# FXIMU.net
KiCad netlist of a schematic drawn in EAGLE
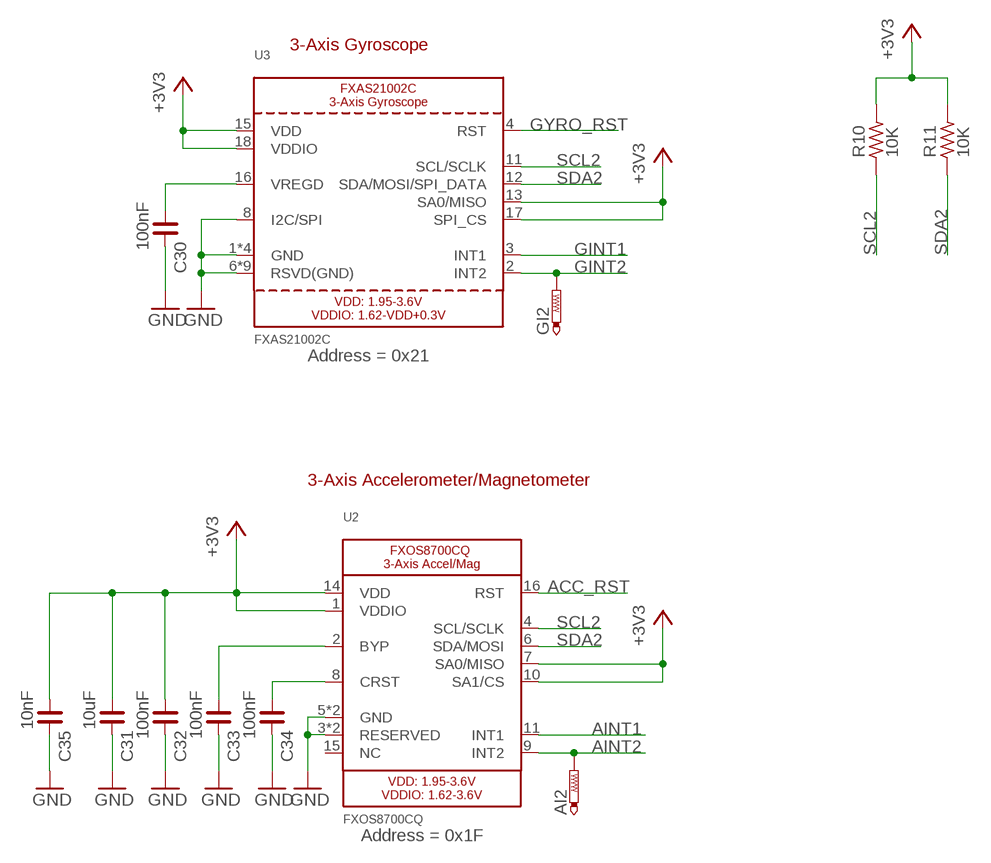
[diagram p0: schematic, sheet 1]
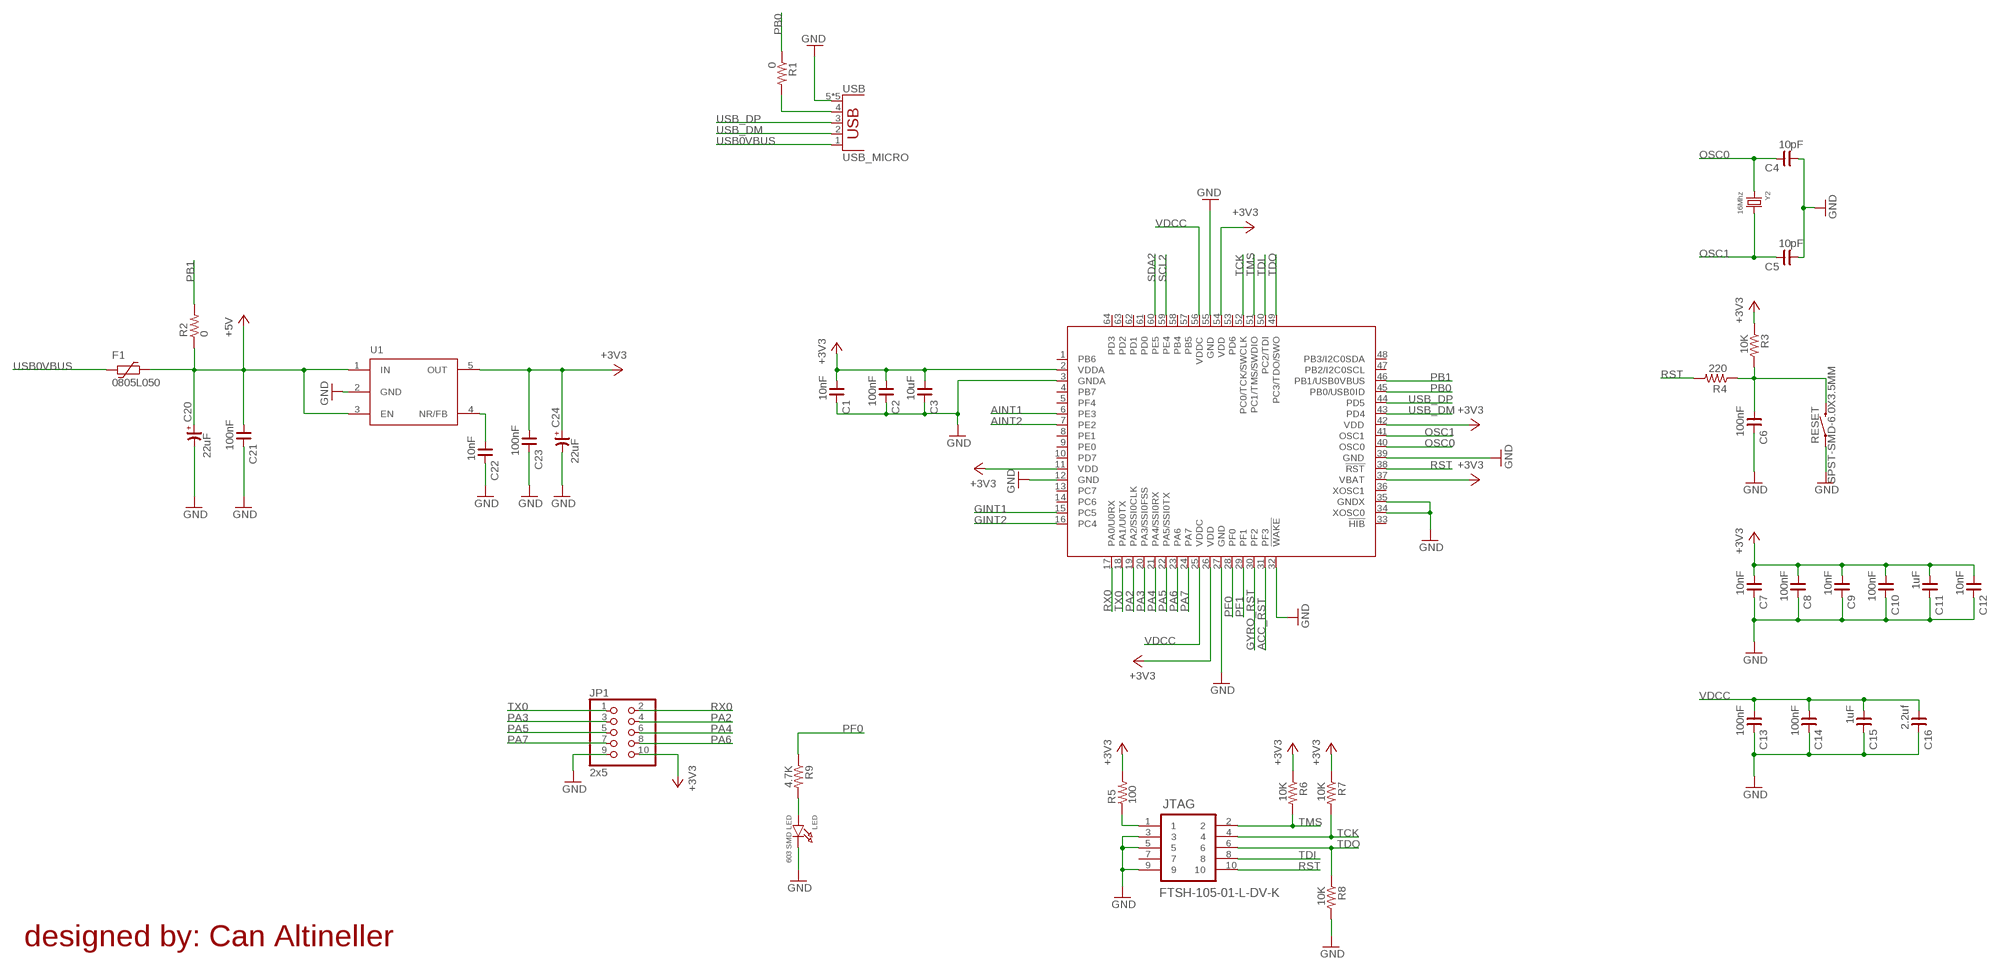
[diagram p1: schematic, sheet 2]

(export (version "E")
  (design (tool "Eeschema 10.0.6"))
  (components
    (comp (ref "AI2")
      (value "PTR1TP06R")
      (footprint "eagle-import:TP06R")
      (libsource (lib "eagle-import") (part "PTR1TP06R"))
    )
    (comp (ref "C30")
      (value "100nF")
      (footprint "eagle-import:C0402")
      (libsource (lib "eagle-import") (part "C_0402"))
    )
    (comp (ref "C31")
      (value "10uF")
      (footprint "eagle-import:C0603")
      (libsource (lib "eagle-import") (part "C_0603"))
    )
    (comp (ref "C32")
      (value "100nF")
      (footprint "eagle-import:C0402")
      (libsource (lib "eagle-import") (part "C_0402"))
    )
    (comp (ref "C33")
      (value "100nF")
      (footprint "eagle-import:C0402")
      (libsource (lib "eagle-import") (part "C_0402"))
    )
    (comp (ref "C34")
      (value "100nF")
      (footprint "eagle-import:C0402")
      (libsource (lib "eagle-import") (part "C_0402"))
    )
    (comp (ref "C35")
      (value "10nF")
      (footprint "eagle-import:C0402")
      (libsource (lib "eagle-import") (part "C_0402"))
    )
    (comp (ref "GI2")
      (value "PTR1TP06R")
      (footprint "eagle-import:TP06R")
      (libsource (lib "eagle-import") (part "PTR1TP06R"))
    )
    (comp (ref "R10")
      (value "10K")
      (footprint "eagle-import:R0402")
      (libsource (lib "eagle-import") (part "R_0402"))
    )
    (comp (ref "R11")
      (value "10K")
      (footprint "eagle-import:R0402")
      (libsource (lib "eagle-import") (part "R_0402"))
    )
    (comp (ref "U2")
      (value "FXOS8700CQ")
      (footprint "eagle-import:QFN16_3MM_FREESCALE_5X3")
      (libsource (lib "eagle-import") (part "ACCEL_MAG_FXOS8700CQ"))
    )
    (comp (ref "U3")
      (value "FXAS21002C")
      (footprint "eagle-import:QFN24_4MM_FREESCALE_7X5")
      (libsource (lib "eagle-import") (part "GYRO_FXAS21002C"))
    )
    (comp (ref "C1")
      (value "10nF")
      (footprint "eagle-import:C0402")
      (libsource (lib "eagle-import") (part "C_0402"))
    )
    (comp (ref "C2")
      (value "100nF")
      (footprint "eagle-import:C0402")
      (libsource (lib "eagle-import") (part "C_0402"))
    )
    (comp (ref "C3")
      (value "10uF")
      (footprint "eagle-import:C0603")
      (libsource (lib "eagle-import") (part "C_0603"))
    )
    (comp (ref "C4")
      (value "10pF")
      (footprint "eagle-import:C0402")
      (libsource (lib "eagle-import") (part "C_0402"))
    )
    (comp (ref "C5")
      (value "10pF")
      (footprint "eagle-import:C0402")
      (libsource (lib "eagle-import") (part "C_0402"))
    )
    (comp (ref "C6")
      (value "100nF")
      (footprint "eagle-import:C0402")
      (libsource (lib "eagle-import") (part "C_0402"))
    )
    (comp (ref "C7")
      (value "10nF")
      (footprint "eagle-import:C0402")
      (libsource (lib "eagle-import") (part "C_0402"))
    )
    (comp (ref "C8")
      (value "100nF")
      (footprint "eagle-import:C0402")
      (libsource (lib "eagle-import") (part "C_0402"))
    )
    (comp (ref "C9")
      (value "10nF")
      (footprint "eagle-import:C0402")
      (libsource (lib "eagle-import") (part "C_0402"))
    )
    (comp (ref "C10")
      (value "100nF")
      (footprint "eagle-import:C0402")
      (libsource (lib "eagle-import") (part "C_0402"))
    )
    (comp (ref "C11")
      (value "1uF")
      (footprint "eagle-import:C0402")
      (libsource (lib "eagle-import") (part "C_0402"))
    )
    (comp (ref "C12")
      (value "10nF")
      (footprint "eagle-import:C0402")
      (libsource (lib "eagle-import") (part "C_0402"))
    )
    (comp (ref "C13")
      (value "100nF")
      (footprint "eagle-import:C0402")
      (libsource (lib "eagle-import") (part "C_0402"))
    )
    (comp (ref "C14")
      (value "100nF")
      (footprint "eagle-import:C0402")
      (libsource (lib "eagle-import") (part "C_0402"))
    )
    (comp (ref "C15")
      (value "1uF")
      (footprint "eagle-import:C0402")
      (libsource (lib "eagle-import") (part "C_0402"))
    )
    (comp (ref "C16")
      (value "2.2uf")
      (footprint "eagle-import:C0603")
      (libsource (lib "eagle-import") (part "C_0603"))
    )
    (comp (ref "C20")
      (value "22uF")
      (footprint "eagle-import:C3528-21_T")
      (libsource (lib "eagle-import") (part "CP_3528-21"))
    )
    (comp (ref "C21")
      (value "100nF")
      (footprint "eagle-import:C0402")
      (libsource (lib "eagle-import") (part "C_0402"))
    )
    (comp (ref "C22")
      (value "10nF")
      (footprint "eagle-import:C0402")
      (libsource (lib "eagle-import") (part "C_0402"))
    )
    (comp (ref "C23")
      (value "100nF")
      (footprint "eagle-import:C0402")
      (libsource (lib "eagle-import") (part "C_0402"))
    )
    (comp (ref "C24")
      (value "22uF")
      (footprint "eagle-import:C3528-21_T")
      (libsource (lib "eagle-import") (part "CP_3528-21"))
    )
    (comp (ref "F1")
      (value "0805L050")
      (footprint "eagle-import:0805L")
      (fields (field (name "MF") "Littelfuse"))
      (libsource (lib "eagle-import") (part "?0805L050"))
    )
    (comp (ref "IC1")
      (value "TM4C123[7,G]XXPM")
      (footprint "eagle-import:PM_S-PQFP-G64")
      (libsource (lib "eagle-import") (part "TM4C123[7,G]XXPM"))
    )
    (comp (ref "JP1")
      (value "2x5")
      (footprint "eagle-import:2X05")
      (libsource (lib "eagle-import") (part "PINHD-2X5"))
    )
    (comp (ref "JTAG")
      (value "FTSH-105-01-L-DV-K")
      (footprint "eagle-import:SAMTEC_FTSH-105-01-L-DV-K")
      (fields (field (name "MF") "Samtec"))
      (libsource (lib "eagle-import") (part "FTSH-105-01-L-DV-K"))
    )
    (comp (ref "LED")
      (value "603 SMD LED")
      (footprint "eagle-import:CHIPLED_0603")
      (libsource (lib "eagle-import") (part "LED0603"))
    )
    (comp (ref "R1")
      (value "0")
      (footprint "eagle-import:R0402")
      (libsource (lib "eagle-import") (part "R_0402"))
    )
    (comp (ref "R2")
      (value "0")
      (footprint "eagle-import:R0402")
      (libsource (lib "eagle-import") (part "R_0402"))
    )
    (comp (ref "R3")
      (value "10K")
      (footprint "eagle-import:R0402")
      (libsource (lib "eagle-import") (part "R_0402"))
    )
    (comp (ref "R4")
      (value "220")
      (footprint "eagle-import:R0402")
      (libsource (lib "eagle-import") (part "R_0402"))
    )
    (comp (ref "R5")
      (value "100")
      (footprint "eagle-import:R0402")
      (libsource (lib "eagle-import") (part "R_0402"))
    )
    (comp (ref "R6")
      (value "10K")
      (footprint "eagle-import:R0402")
      (libsource (lib "eagle-import") (part "R_0402"))
    )
    (comp (ref "R7")
      (value "10K")
      (footprint "eagle-import:R0402")
      (libsource (lib "eagle-import") (part "R_0402"))
    )
    (comp (ref "R8")
      (value "10K")
      (footprint "eagle-import:R0402")
      (libsource (lib "eagle-import") (part "R_0402"))
    )
    (comp (ref "R9")
      (value "4.7K")
      (footprint "eagle-import:R0402")
      (libsource (lib "eagle-import") (part "R_0402"))
    )
    (comp (ref "RESET")
      (value "SPST-SMD-6.0X3.5MM")
      (footprint "eagle-import:TACTILE_SWITCH_SMD_6.0X3.5MM")
      (libsource (lib "eagle-import") (part "MOMENTARY-SWITCH-SPST-SMD-6.0X3.5MM"))
    )
    (comp (ref "U1")
      (value "TPS73633")
      (footprint "eagle-import:SOT23-5L")
      (libsource (lib "eagle-import") (part "TPS73633"))
    )
    (comp (ref "USB")
      (value "USB_MICRO")
      (footprint "eagle-import:USB_MICRO_MOLEX_FULL")
      (libsource (lib "eagle-import") (part "USB_MICRO"))
    )
    (comp (ref "Y2")
      (value "16Mhz")
      (footprint "eagle-import:6X3.3MM")
      (libsource (lib "eagle-import") (part "CRYSTAL.6X3.3MM"))
    )
  )
  (nets
    (net (code "1") (name "+3V3") (class "Default")
      (node (ref "C1") (pin "1") (pinfunction "1_1") (pintype "passive"))
      (node (ref "C10") (pin "1") (pinfunction "1_1") (pintype "passive"))
      (node (ref "C11") (pin "1") (pinfunction "1_1") (pintype "passive"))
      (node (ref "C12") (pin "1") (pinfunction "1_1") (pintype "passive"))
      (node (ref "C2") (pin "1") (pinfunction "1_1") (pintype "passive"))
      (node (ref "C23") (pin "1") (pinfunction "1_1") (pintype "passive"))
      (node (ref "C24") (pin "+") (pinfunction "+_+") (pintype "passive"))
      (node (ref "C3") (pin "1") (pinfunction "1_1") (pintype "passive"))
      (node (ref "C31") (pin "1") (pinfunction "1_1") (pintype "passive"))
      (node (ref "C32") (pin "1") (pinfunction "1_1") (pintype "passive"))
      (node (ref "C35") (pin "1") (pinfunction "1_1") (pintype "passive"))
      (node (ref "C7") (pin "1") (pinfunction "1_1") (pintype "passive"))
      (node (ref "C8") (pin "1") (pinfunction "1_1") (pintype "passive"))
      (node (ref "C9") (pin "1") (pinfunction "1_1") (pintype "passive"))
      (node (ref "IC1") (pin "11") (pinfunction "VDD_11") (pintype "bidirectional"))
      (node (ref "IC1") (pin "2") (pinfunction "VDDA_2") (pintype "bidirectional"))
      (node (ref "IC1") (pin "26") (pinfunction "VDD_26") (pintype "bidirectional"))
      (node (ref "IC1") (pin "37") (pinfunction "VBAT_37") (pintype "bidirectional"))
      (node (ref "IC1") (pin "42") (pinfunction "VDD_42") (pintype "bidirectional"))
      (node (ref "IC1") (pin "54") (pinfunction "VDD_54") (pintype "bidirectional"))
      (node (ref "JP1") (pin "10") (pinfunction "10_10") (pintype "passive"))
      (node (ref "R10") (pin "2") (pinfunction "2_2") (pintype "passive"))
      (node (ref "R11") (pin "2") (pinfunction "2_2") (pintype "passive"))
      (node (ref "R3") (pin "1") (pinfunction "1_1") (pintype "passive"))
      (node (ref "R5") (pin "2") (pinfunction "2_2") (pintype "passive"))
      (node (ref "R6") (pin "1") (pinfunction "1_1") (pintype "passive"))
      (node (ref "R7") (pin "1") (pinfunction "1_1") (pintype "passive"))
      (node (ref "U1") (pin "5") (pinfunction "OUT_5") (pintype "bidirectional"))
      (node (ref "U2") (pin "1") (pinfunction "VDDIO_1") (pintype "bidirectional"))
      (node (ref "U2") (pin "10") (pinfunction "SA1/CS_10") (pintype "bidirectional"))
      (node (ref "U2") (pin "14") (pinfunction "VDD_14") (pintype "bidirectional"))
      (node (ref "U2") (pin "7") (pinfunction "SA0/MISO_7") (pintype "bidirectional"))
      (node (ref "U3") (pin "13") (pinfunction "SA0/MISO_13") (pintype "bidirectional"))
      (node (ref "U3") (pin "15") (pinfunction "VDD_15") (pintype "bidirectional"))
      (node (ref "U3") (pin "17") (pinfunction "SPI_CS_17") (pintype "bidirectional"))
      (node (ref "U3") (pin "18") (pinfunction "VDDIO_18") (pintype "bidirectional"))
    )
    (net (code "2") (name "+5V") (class "Default")
      (node (ref "C20") (pin "+") (pinfunction "+_+") (pintype "passive"))
      (node (ref "C21") (pin "1") (pinfunction "1_1") (pintype "passive"))
      (node (ref "F1") (pin "1") (pinfunction "1_1") (pintype "passive"))
      (node (ref "R2") (pin "1") (pinfunction "1_1") (pintype "passive"))
      (node (ref "U1") (pin "1") (pinfunction "IN_1") (pintype "bidirectional"))
      (node (ref "U1") (pin "3") (pinfunction "EN_3") (pintype "bidirectional"))
    )
    (net (code "3") (name "ACC_RST") (class "Default")
      (node (ref "IC1") (pin "31") (pinfunction "PF3_31") (pintype "bidirectional"))
      (node (ref "U2") (pin "16") (pinfunction "RST_16") (pintype "bidirectional"))
    )
    (net (code "4") (name "AINT1") (class "Default")
      (node (ref "IC1") (pin "6") (pinfunction "PE3_6") (pintype "bidirectional"))
      (node (ref "U2") (pin "11") (pinfunction "INT1_11") (pintype "bidirectional"))
    )
    (net (code "5") (name "AINT2") (class "Default")
      (node (ref "AI2") (pin "TP") (pinfunction "TP_TP") (pintype "input"))
      (node (ref "IC1") (pin "7") (pinfunction "PE2_7") (pintype "bidirectional"))
      (node (ref "U2") (pin "9") (pinfunction "INT2_9") (pintype "bidirectional"))
    )
    (net (code "6") (name "GINT1") (class "Default")
      (node (ref "IC1") (pin "15") (pinfunction "PC5_15") (pintype "bidirectional"))
      (node (ref "U3") (pin "3") (pinfunction "INT1_3") (pintype "bidirectional"))
    )
    (net (code "7") (name "GINT2") (class "Default")
      (node (ref "GI2") (pin "TP") (pinfunction "TP_TP") (pintype "input"))
      (node (ref "IC1") (pin "16") (pinfunction "PC4_16") (pintype "bidirectional"))
      (node (ref "U3") (pin "2") (pinfunction "INT2_2") (pintype "bidirectional"))
    )
    (net (code "8") (name "GND") (class "Default")
      (node (ref "C1") (pin "2") (pinfunction "2_2") (pintype "passive"))
      (node (ref "C10") (pin "2") (pinfunction "2_2") (pintype "passive"))
      (node (ref "C11") (pin "2") (pinfunction "2_2") (pintype "passive"))
      (node (ref "C12") (pin "2") (pinfunction "2_2") (pintype "passive"))
      (node (ref "C13") (pin "2") (pinfunction "2_2") (pintype "passive"))
      (node (ref "C14") (pin "2") (pinfunction "2_2") (pintype "passive"))
      (node (ref "C15") (pin "2") (pinfunction "2_2") (pintype "passive"))
      (node (ref "C16") (pin "2") (pinfunction "2_2") (pintype "passive"))
      (node (ref "C2") (pin "2") (pinfunction "2_2") (pintype "passive"))
      (node (ref "C20") (pin "-") (pinfunction "-_-") (pintype "passive"))
      (node (ref "C21") (pin "2") (pinfunction "2_2") (pintype "passive"))
      (node (ref "C22") (pin "2") (pinfunction "2_2") (pintype "passive"))
      (node (ref "C23") (pin "2") (pinfunction "2_2") (pintype "passive"))
      (node (ref "C24") (pin "-") (pinfunction "-_-") (pintype "passive"))
      (node (ref "C3") (pin "2") (pinfunction "2_2") (pintype "passive"))
      (node (ref "C30") (pin "2") (pinfunction "2_2") (pintype "passive"))
      (node (ref "C31") (pin "2") (pinfunction "2_2") (pintype "passive"))
      (node (ref "C32") (pin "2") (pinfunction "2_2") (pintype "passive"))
      (node (ref "C33") (pin "2") (pinfunction "2_2") (pintype "passive"))
      (node (ref "C34") (pin "2") (pinfunction "2_2") (pintype "passive"))
      (node (ref "C35") (pin "2") (pinfunction "2_2") (pintype "passive"))
      (node (ref "C4") (pin "1") (pinfunction "1_1") (pintype "passive"))
      (node (ref "C5") (pin "1") (pinfunction "1_1") (pintype "passive"))
      (node (ref "C6") (pin "2") (pinfunction "2_2") (pintype "passive"))
      (node (ref "C7") (pin "2") (pinfunction "2_2") (pintype "passive"))
      (node (ref "C8") (pin "2") (pinfunction "2_2") (pintype "passive"))
      (node (ref "C9") (pin "2") (pinfunction "2_2") (pintype "passive"))
      (node (ref "IC1") (pin "12") (pinfunction "GND_12") (pintype "bidirectional"))
      (node (ref "IC1") (pin "27") (pinfunction "GND_27") (pintype "bidirectional"))
      (node (ref "IC1") (pin "3") (pinfunction "GNDA_3") (pintype "bidirectional"))
      (node (ref "IC1") (pin "32") (pinfunction "~{WAKE}_32") (pintype "bidirectional"))
      (node (ref "IC1") (pin "34") (pinfunction "XOSC0_34") (pintype "bidirectional"))
      (node (ref "IC1") (pin "35") (pinfunction "GNDX_35") (pintype "bidirectional"))
      (node (ref "IC1") (pin "39") (pinfunction "GND_39") (pintype "bidirectional"))
      (node (ref "IC1") (pin "55") (pinfunction "GND_55") (pintype "bidirectional"))
      (node (ref "JP1") (pin "9") (pinfunction "9_9") (pintype "passive"))
      (node (ref "JTAG") (pin "3") (pinfunction "3_3") (pintype "passive"))
      (node (ref "JTAG") (pin "5") (pinfunction "5_5") (pintype "passive"))
      (node (ref "JTAG") (pin "9") (pinfunction "9_9") (pintype "passive"))
      (node (ref "LED") (pin "C") (pinfunction "C_C") (pintype "passive"))
      (node (ref "R8") (pin "2") (pinfunction "2_2") (pintype "passive"))
      (node (ref "RESET") (pin "1") (pinfunction "1_1") (pintype "passive"))
      (node (ref "U1") (pin "2") (pinfunction "GND_2") (pintype "bidirectional"))
      (node (ref "U2") (pin "12") (pinfunction "GND_12") (pintype "bidirectional"))
      (node (ref "U2") (pin "13") (pinfunction "RESERVED_13") (pintype "bidirectional"))
      (node (ref "U2") (pin "3") (pinfunction "RESERVED_3") (pintype "bidirectional"))
      (node (ref "U2") (pin "5") (pinfunction "GND_5") (pintype "bidirectional"))
      (node (ref "U3") (pin "1") (pinfunction "GND_1") (pintype "bidirectional"))
      (node (ref "U3") (pin "10") (pinfunction "RSVD(GND)_10") (pintype "bidirectional"))
      (node (ref "U3") (pin "14") (pinfunction "GND_14") (pintype "bidirectional"))
      (node (ref "U3") (pin "19") (pinfunction "GND_19") (pintype "bidirectional"))
      (node (ref "U3") (pin "20") (pinfunction "RSVD(GND)_20") (pintype "bidirectional"))
      (node (ref "U3") (pin "21") (pinfunction "RSVD(GND)_21") (pintype "bidirectional"))
      (node (ref "U3") (pin "22") (pinfunction "RSVD(GND)_22") (pintype "bidirectional"))
      (node (ref "U3") (pin "23") (pinfunction "RSVD(GND)_23") (pintype "bidirectional"))
      (node (ref "U3") (pin "24") (pinfunction "RSVD(GND)_24") (pintype "bidirectional"))
      (node (ref "U3") (pin "5") (pinfunction "GND_5") (pintype "bidirectional"))
      (node (ref "U3") (pin "6") (pinfunction "RSVD(GND)_6") (pintype "bidirectional"))
      (node (ref "U3") (pin "7") (pinfunction "RSVD(GND)_7") (pintype "bidirectional"))
      (node (ref "U3") (pin "8") (pinfunction "I2C/SPI_8") (pintype "bidirectional"))
      (node (ref "U3") (pin "9") (pinfunction "RSVD(GND)_9") (pintype "bidirectional"))
      (node (ref "USB") (pin "5") (pinfunction "GND_5") (pintype "bidirectional"))
      (node (ref "USB") (pin "P$1") (pinfunction "GND_P$1") (pintype "bidirectional"))
      (node (ref "USB") (pin "P$2") (pinfunction "GND_P$2") (pintype "bidirectional"))
      (node (ref "USB") (pin "P$3") (pinfunction "GND_P$3") (pintype "bidirectional"))
      (node (ref "USB") (pin "P$4") (pinfunction "GND_P$4") (pintype "bidirectional"))
    )
    (net (code "9") (name "GYRO_RST") (class "Default")
      (node (ref "IC1") (pin "30") (pinfunction "PF2_30") (pintype "bidirectional"))
      (node (ref "U3") (pin "4") (pinfunction "RST_4") (pintype "bidirectional"))
    )
    (net (code "10") (name "Net-(C6-Pad1)") (class "Default")
      (node (ref "C6") (pin "1") (pinfunction "1_1") (pintype "passive"))
      (node (ref "R3") (pin "2") (pinfunction "2_2") (pintype "passive"))
      (node (ref "R4") (pin "1") (pinfunction "1_1") (pintype "passive"))
      (node (ref "RESET") (pin "2") (pinfunction "2_2") (pintype "passive"))
    )
    (net (code "11") (name "Net-(JTAG-Pad1)") (class "Default")
      (node (ref "JTAG") (pin "1") (pinfunction "1_1") (pintype "passive"))
      (node (ref "R5") (pin "1") (pinfunction "1_1") (pintype "passive"))
    )
    (net (code "12") (name "Net-(LED-PadA)") (class "Default")
      (node (ref "LED") (pin "A") (pinfunction "A_A") (pintype "passive"))
      (node (ref "R9") (pin "2") (pinfunction "2_2") (pintype "passive"))
    )
    (net (code "13") (name "Net-(U1-NR{slash}FB)") (class "Default")
      (node (ref "C22") (pin "1") (pinfunction "1_1") (pintype "passive"))
      (node (ref "U1") (pin "4") (pinfunction "NR/FB_4") (pintype "bidirectional"))
    )
    (net (code "14") (name "Net-(U2-BYP)") (class "Default")
      (node (ref "C33") (pin "1") (pinfunction "1_1") (pintype "passive"))
      (node (ref "U2") (pin "2") (pinfunction "BYP_2") (pintype "bidirectional"))
    )
    (net (code "15") (name "Net-(U2-CRST)") (class "Default")
      (node (ref "C34") (pin "1") (pinfunction "1_1") (pintype "passive"))
      (node (ref "U2") (pin "8") (pinfunction "CRST_8") (pintype "bidirectional"))
    )
    (net (code "16") (name "Net-(U3-VREGD)") (class "Default")
      (node (ref "C30") (pin "1") (pinfunction "1_1") (pintype "passive"))
      (node (ref "U3") (pin "16") (pinfunction "VREGD_16") (pintype "bidirectional"))
    )
    (net (code "17") (name "Net-(USB-ID)") (class "Default")
      (node (ref "R1") (pin "2") (pinfunction "2_2") (pintype "passive"))
      (node (ref "USB") (pin "4") (pinfunction "ID_4") (pintype "bidirectional"))
    )
    (net (code "18") (name "OSC0") (class "Default")
      (node (ref "C4") (pin "2") (pinfunction "2_2") (pintype "passive"))
      (node (ref "IC1") (pin "40") (pinfunction "OSC0_40") (pintype "bidirectional"))
      (node (ref "Y2") (pin "1") (pinfunction "1_1") (pintype "passive"))
    )
    (net (code "19") (name "OSC1") (class "Default")
      (node (ref "C5") (pin "2") (pinfunction "2_2") (pintype "passive"))
      (node (ref "IC1") (pin "41") (pinfunction "OSC1_41") (pintype "bidirectional"))
      (node (ref "Y2") (pin "2") (pinfunction "2_2") (pintype "passive"))
    )
    (net (code "20") (name "PA2") (class "Default")
      (node (ref "IC1") (pin "19") (pinfunction "PA2/SSI0CLK_19") (pintype "bidirectional"))
      (node (ref "JP1") (pin "4") (pinfunction "4_4") (pintype "passive"))
    )
    (net (code "21") (name "PA3") (class "Default")
      (node (ref "IC1") (pin "20") (pinfunction "PA3/SSI0FSS_20") (pintype "bidirectional"))
      (node (ref "JP1") (pin "3") (pinfunction "3_3") (pintype "passive"))
    )
    (net (code "22") (name "PA4") (class "Default")
      (node (ref "IC1") (pin "21") (pinfunction "PA4/SSI0RX_21") (pintype "bidirectional"))
      (node (ref "JP1") (pin "6") (pinfunction "6_6") (pintype "passive"))
    )
    (net (code "23") (name "PA5") (class "Default")
      (node (ref "IC1") (pin "22") (pinfunction "PA5/SSI0TX_22") (pintype "bidirectional"))
      (node (ref "JP1") (pin "5") (pinfunction "5_5") (pintype "passive"))
    )
    (net (code "24") (name "PA6") (class "Default")
      (node (ref "IC1") (pin "23") (pinfunction "PA6_23") (pintype "bidirectional"))
      (node (ref "JP1") (pin "8") (pinfunction "8_8") (pintype "passive"))
    )
    (net (code "25") (name "PA7") (class "Default")
      (node (ref "IC1") (pin "24") (pinfunction "PA7_24") (pintype "bidirectional"))
      (node (ref "JP1") (pin "7") (pinfunction "7_7") (pintype "passive"))
    )
    (net (code "26") (name "PB0") (class "Default")
      (node (ref "IC1") (pin "45") (pinfunction "PB0/USB0ID_45") (pintype "bidirectional"))
      (node (ref "R1") (pin "1") (pinfunction "1_1") (pintype "passive"))
    )
    (net (code "27") (name "PB1") (class "Default")
      (node (ref "IC1") (pin "46") (pinfunction "PB1/USB0VBUS_46") (pintype "bidirectional"))
      (node (ref "R2") (pin "2") (pinfunction "2_2") (pintype "passive"))
    )
    (net (code "28") (name "PF0") (class "Default")
      (node (ref "IC1") (pin "28") (pinfunction "PF0_28") (pintype "bidirectional"))
      (node (ref "R9") (pin "1") (pinfunction "1_1") (pintype "passive"))
    )
    (net (code "29") (name "PF1") (class "Default")
      (node (ref "IC1") (pin "29") (pinfunction "PF1_29") (pintype "bidirectional"))
    )
    (net (code "30") (name "RST") (class "Default")
      (node (ref "IC1") (pin "38") (pinfunction "~{RST}_38") (pintype "bidirectional"))
      (node (ref "JTAG") (pin "10") (pinfunction "10_10") (pintype "passive"))
      (node (ref "R4") (pin "2") (pinfunction "2_2") (pintype "passive"))
    )
    (net (code "31") (name "RX0") (class "Default")
      (node (ref "IC1") (pin "17") (pinfunction "PA0/U0RX_17") (pintype "bidirectional"))
      (node (ref "JP1") (pin "2") (pinfunction "2_2") (pintype "passive"))
    )
    (net (code "32") (name "SCL2") (class "Default")
      (node (ref "IC1") (pin "59") (pinfunction "PE4_59") (pintype "bidirectional"))
      (node (ref "R10") (pin "1") (pinfunction "1_1") (pintype "passive"))
      (node (ref "U2") (pin "4") (pinfunction "SCL/SCLK_4") (pintype "bidirectional"))
      (node (ref "U3") (pin "11") (pinfunction "SCL/SCLK_11") (pintype "bidirectional"))
    )
    (net (code "33") (name "SDA2") (class "Default")
      (node (ref "IC1") (pin "60") (pinfunction "PE5_60") (pintype "bidirectional"))
      (node (ref "R11") (pin "1") (pinfunction "1_1") (pintype "passive"))
      (node (ref "U2") (pin "6") (pinfunction "SDA/MOSI_6") (pintype "bidirectional"))
      (node (ref "U3") (pin "12") (pinfunction "SDA/MOSI/SPI_DATA_12") (pintype "bidirectional"))
    )
    (net (code "34") (name "TCK") (class "Default")
      (node (ref "IC1") (pin "52") (pinfunction "PC0/TCK/SWCLK_52") (pintype "bidirectional"))
      (node (ref "JTAG") (pin "4") (pinfunction "4_4") (pintype "passive"))
      (node (ref "R7") (pin "2") (pinfunction "2_2") (pintype "passive"))
    )
    (net (code "35") (name "TDI") (class "Default")
      (node (ref "IC1") (pin "50") (pinfunction "PC2/TDI_50") (pintype "bidirectional"))
      (node (ref "JTAG") (pin "8") (pinfunction "8_8") (pintype "passive"))
    )
    (net (code "36") (name "TDO") (class "Default")
      (node (ref "IC1") (pin "49") (pinfunction "PC3/TDO/SWO_49") (pintype "bidirectional"))
      (node (ref "JTAG") (pin "6") (pinfunction "6_6") (pintype "passive"))
      (node (ref "R8") (pin "1") (pinfunction "1_1") (pintype "passive"))
    )
    (net (code "37") (name "TMS") (class "Default")
      (node (ref "IC1") (pin "51") (pinfunction "PC1/TMS/SWDIO_51") (pintype "bidirectional"))
      (node (ref "JTAG") (pin "2") (pinfunction "2_2") (pintype "passive"))
      (node (ref "R6") (pin "2") (pinfunction "2_2") (pintype "passive"))
    )
    (net (code "38") (name "TX0") (class "Default")
      (node (ref "IC1") (pin "18") (pinfunction "PA1/U0TX_18") (pintype "bidirectional"))
      (node (ref "JP1") (pin "1") (pinfunction "1_1") (pintype "passive"))
    )
    (net (code "39") (name "USB0VBUS") (class "Default")
      (node (ref "F1") (pin "2") (pinfunction "2_2") (pintype "passive"))
      (node (ref "USB") (pin "1") (pinfunction "VBUS_1") (pintype "bidirectional"))
    )
    (net (code "40") (name "USB_DM") (class "Default")
      (node (ref "IC1") (pin "43") (pinfunction "PD4_43") (pintype "bidirectional"))
      (node (ref "USB") (pin "2") (pinfunction "D-_2") (pintype "bidirectional"))
    )
    (net (code "41") (name "USB_DP") (class "Default")
      (node (ref "IC1") (pin "44") (pinfunction "PD5_44") (pintype "bidirectional"))
      (node (ref "USB") (pin "3") (pinfunction "D+_3") (pintype "bidirectional"))
    )
    (net (code "42") (name "VDCC") (class "Default")
      (node (ref "C13") (pin "1") (pinfunction "1_1") (pintype "passive"))
      (node (ref "C14") (pin "1") (pinfunction "1_1") (pintype "passive"))
      (node (ref "C15") (pin "1") (pinfunction "1_1") (pintype "passive"))
      (node (ref "C16") (pin "1") (pinfunction "1_1") (pintype "passive"))
      (node (ref "IC1") (pin "25") (pinfunction "VDDC_25") (pintype "bidirectional"))
      (node (ref "IC1") (pin "56") (pinfunction "VDDC_56") (pintype "bidirectional"))
    )
    (net (code "43") (name "unconnected-(IC1-PB2{slash}I2C0SCL-Pad47)") (class "Default")
      (node (ref "IC1") (pin "47") (pinfunction "PB2/I2C0SCL_47") (pintype "bidirectional"))
    )
    (net (code "44") (name "unconnected-(IC1-PB3{slash}I2C0SDA-Pad48)") (class "Default")
      (node (ref "IC1") (pin "48") (pinfunction "PB3/I2C0SDA_48") (pintype "bidirectional"))
    )
    (net (code "45") (name "unconnected-(IC1-PB4-Pad58)") (class "Default")
      (node (ref "IC1") (pin "58") (pinfunction "PB4_58") (pintype "bidirectional"))
    )
    (net (code "46") (name "unconnected-(IC1-PB5-Pad57)") (class "Default")
      (node (ref "IC1") (pin "57") (pinfunction "PB5_57") (pintype "bidirectional"))
    )
    (net (code "47") (name "unconnected-(IC1-PB6-Pad1)") (class "Default")
      (node (ref "IC1") (pin "1") (pinfunction "PB6_1") (pintype "bidirectional"))
    )
    (net (code "48") (name "unconnected-(IC1-PB7-Pad4)") (class "Default")
      (node (ref "IC1") (pin "4") (pinfunction "PB7_4") (pintype "bidirectional"))
    )
    (net (code "49") (name "unconnected-(IC1-PC6-Pad14)") (class "Default")
      (node (ref "IC1") (pin "14") (pinfunction "PC6_14") (pintype "bidirectional"))
    )
    (net (code "50") (name "unconnected-(IC1-PC7-Pad13)") (class "Default")
      (node (ref "IC1") (pin "13") (pinfunction "PC7_13") (pintype "bidirectional"))
    )
    (net (code "51") (name "unconnected-(IC1-PD0-Pad61)") (class "Default")
      (node (ref "IC1") (pin "61") (pinfunction "PD0_61") (pintype "bidirectional"))
    )
    (net (code "52") (name "unconnected-(IC1-PD1-Pad62)") (class "Default")
      (node (ref "IC1") (pin "62") (pinfunction "PD1_62") (pintype "bidirectional"))
    )
    (net (code "53") (name "unconnected-(IC1-PD2-Pad63)") (class "Default")
      (node (ref "IC1") (pin "63") (pinfunction "PD2_63") (pintype "bidirectional"))
    )
    (net (code "54") (name "unconnected-(IC1-PD3-Pad64)") (class "Default")
      (node (ref "IC1") (pin "64") (pinfunction "PD3_64") (pintype "bidirectional"))
    )
    (net (code "55") (name "unconnected-(IC1-PD6-Pad53)") (class "Default")
      (node (ref "IC1") (pin "53") (pinfunction "PD6_53") (pintype "bidirectional"))
    )
    (net (code "56") (name "unconnected-(IC1-PD7-Pad10)") (class "Default")
      (node (ref "IC1") (pin "10") (pinfunction "PD7_10") (pintype "bidirectional"))
    )
    (net (code "57") (name "unconnected-(IC1-PE0-Pad9)") (class "Default")
      (node (ref "IC1") (pin "9") (pinfunction "PE0_9") (pintype "bidirectional"))
    )
    (net (code "58") (name "unconnected-(IC1-PE1-Pad8)") (class "Default")
      (node (ref "IC1") (pin "8") (pinfunction "PE1_8") (pintype "bidirectional"))
    )
    (net (code "59") (name "unconnected-(IC1-PF4-Pad5)") (class "Default")
      (node (ref "IC1") (pin "5") (pinfunction "PF4_5") (pintype "bidirectional"))
    )
    (net (code "60") (name "unconnected-(IC1-XOSC1-Pad36)") (class "Default")
      (node (ref "IC1") (pin "36") (pinfunction "XOSC1_36") (pintype "bidirectional"))
    )
    (net (code "61") (name "unconnected-(IC1-~{HIB}-Pad33)") (class "Default")
      (node (ref "IC1") (pin "33") (pinfunction "~{HIB}_33") (pintype "bidirectional"))
    )
    (net (code "62") (name "unconnected-(JTAG-Pad7)") (class "Default")
      (node (ref "JTAG") (pin "7") (pinfunction "7_7") (pintype "passive"))
    )
    (net (code "63") (name "unconnected-(U2-NC-Pad15)") (class "Default")
      (node (ref "U2") (pin "15") (pinfunction "NC_15") (pintype "bidirectional"))
    )
  )
)
